# Sheet2.net
KiCad netlist of a schematic drawn in Altium Designer
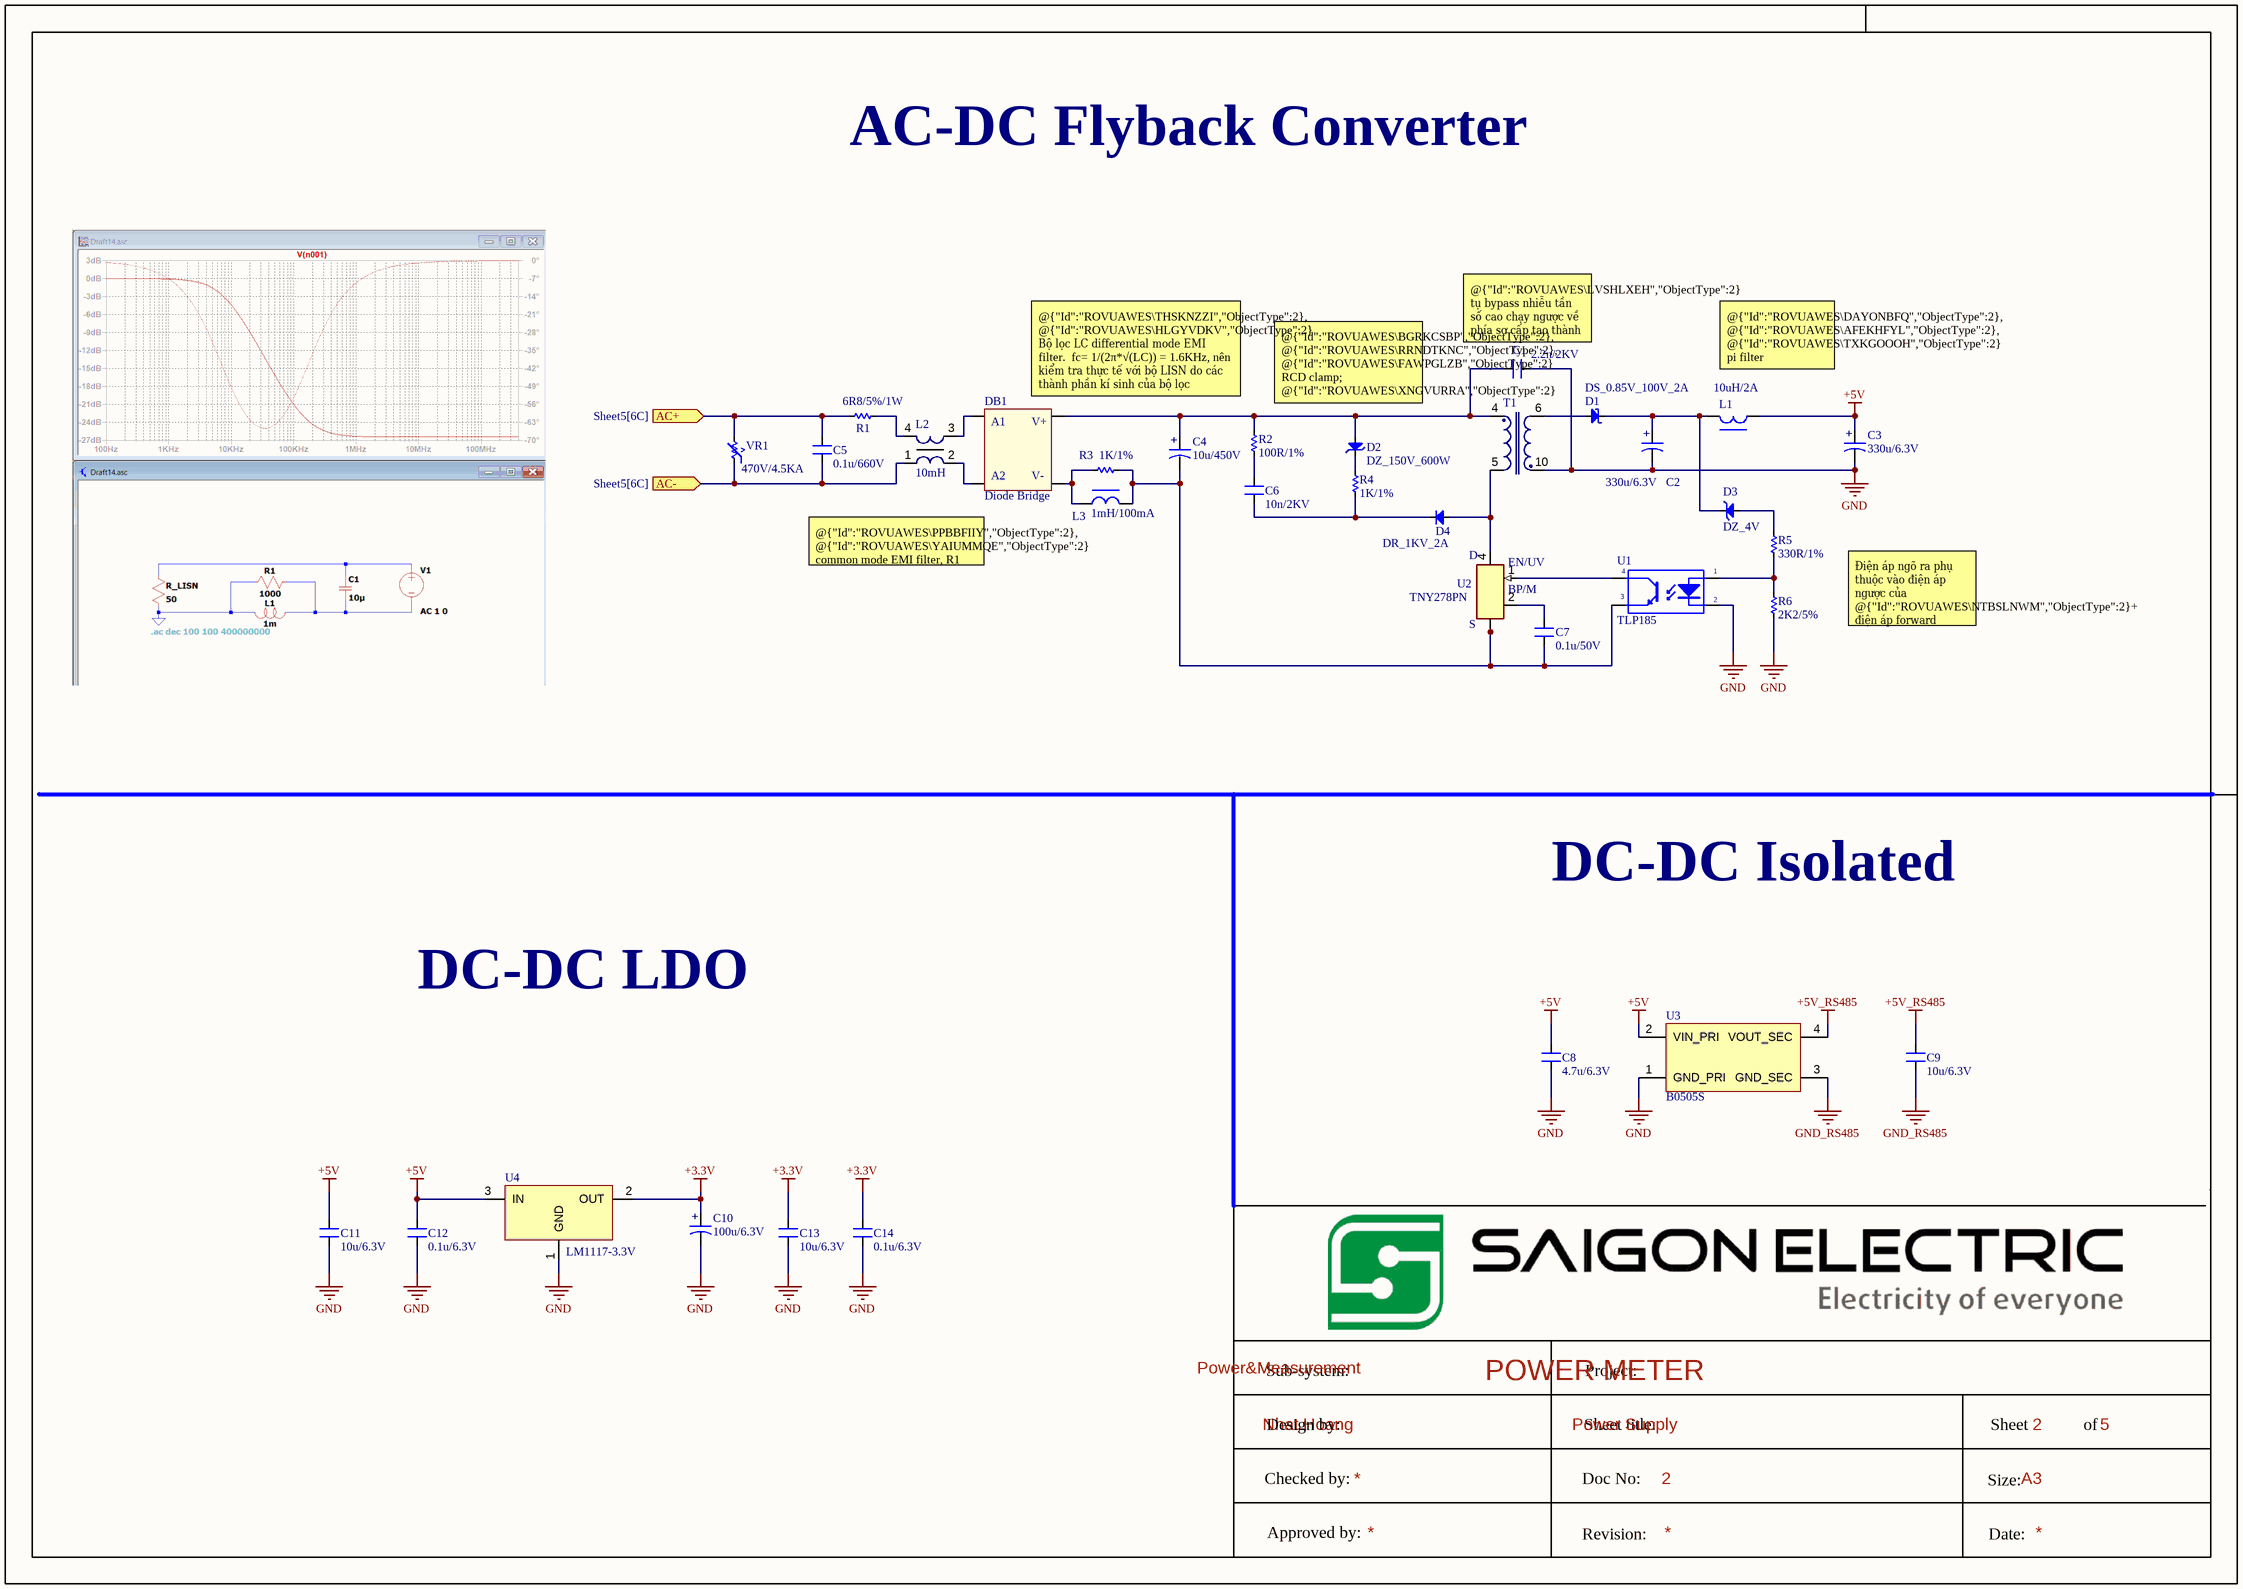
[diagram p0: Sheet2.SchDoc]

(export (version "E")
  (design (tool "Eeschema 10.0.6"))
  (components
    (comp (ref "C1")
      (value "2.2n/2KV")
      (footprint "CN2-B")
      (libsource (lib "DAK_Altium_Integrated_Lib") (part "CAP_SMD"))
    )
    (comp (ref "C2")
      (value "330u/6.3V")
      (footprint "CAPAE9383X105M")
      (fields (field (name "LCSC PART #") "C19606"))
      (libsource (lib "PowerMeter") (part "CAP_POLAR"))
    )
    (comp (ref "C3")
      (value "330u/6.3V")
      (footprint "CAPAE9383X105M")
      (fields (field (name "LCSC PART #") "C19606"))
      (libsource (lib "PowerMeter") (part "CAP_POLAR"))
    )
    (comp (ref "C4")
      (value "10u/450V")
      (footprint "CA-ALU-10BL")
      (libsource (lib "PowerMeter") (part "CAP_POLAR"))
    )
    (comp (ref "C5")
      (value "0.1u/660V")
      (footprint "CAPRR1500W60L1750T900H1600")
      (libsource (lib "DAK_Altium_Integrated_Lib") (part "CAP_SMD"))
    )
    (comp (ref "C6")
      (value "10n/2KV")
      (footprint "CAPRB750W60L1450T500H1850")
      (libsource (lib "DAK_Altium_Integrated_Lib") (part "CAP_SMD"))
    )
    (comp (ref "C7")
      (value "0.1u/50V")
      (footprint "RES_C_3216X70")
      (libsource (lib "DAK_Altium_Integrated_Lib") (part "CAP_SMD"))
    )
    (comp (ref "C8")
      (value "4.7u/6.3V")
      (footprint "CAP_C_2012X110")
      (libsource (lib "DAK_Altium_Integrated_Lib") (part "CAP_SMD"))
    )
    (comp (ref "C9")
      (value "10u/6.3V")
      (footprint "CAP_C_2012X110")
      (libsource (lib "DAK_Altium_Integrated_Lib") (part "CAP_SMD"))
    )
    (comp (ref "C10")
      (value "100u/6.3V")
      (footprint "CAP-ALU-SMD-6.3x7.7x2.2")
      (libsource (lib "PowerMeter") (part "CAP_POLAR"))
    )
    (comp (ref "C11")
      (value "10u/6.3V")
      (footprint "CAP_C_2012X110")
      (libsource (lib "DAK_Altium_Integrated_Lib") (part "CAP_SMD"))
    )
    (comp (ref "C12")
      (value "0.1u/6.3V")
      (footprint "CAP_C_2012X110")
      (libsource (lib "DAK_Altium_Integrated_Lib") (part "CAP_SMD"))
    )
    (comp (ref "C13")
      (value "10u/6.3V")
      (footprint "CAP_C_2012X110")
      (libsource (lib "DAK_Altium_Integrated_Lib") (part "CAP_SMD"))
    )
    (comp (ref "C14")
      (value "0.1u/6.3V")
      (footprint "CAP_C_2012X110")
      (libsource (lib "DAK_Altium_Integrated_Lib") (part "CAP_SMD"))
    )
    (comp (ref "D1")
      (value "DS_0.85V_100V_2A")
      (footprint "DIOM5025X26N")
      (description "Schottky")
      (libsource (lib "PowerMeter") (part "DIODE schottky"))
    )
    (comp (ref "D2")
      (value "DZ_150V_600W")
      (footprint "DIOM4436X26N")
      (description "Zenner")
      (libsource (lib "PowerMeter") (part "DIODE Zener"))
    )
    (comp (ref "D3")
      (value "DZ_4V")
      (footprint "LL-34")
      (description "Zenner")
      (libsource (lib "PowerMeter") (part "DIODE Zener"))
    )
    (comp (ref "D4")
      (value "DR_1KV_2A")
      (footprint "DIOM5025X26N")
      (description "Default Diode")
      (fields (field (name "PUBLISHER") "Altium Limited"))
      (libsource (lib "Library") (part "Diode"))
    )
    (comp (ref "DB1")
      (value "Diode Bridge")
      (footprint "diode bridge 2A")
      (description "Convert AC to DC voltage, 4 pin")
      (libsource (lib "PowerMeter") (part "DIODE BRIGDE"))
    )
    (comp (ref "L1")
      (value "10uH/2A")
      (footprint "L-DIP-M-10")
      (description "Inductor")
      (libsource (lib "Library") (part "L-DIP-1"))
    )
    (comp (ref "L2")
      (value "10mH")
      (footprint "UU98LFH142LF")
      (fields
        (field (name "PARTNO") "744284100")
        (field (name "MANUFACTURER") "Würth Elektronik eiSos GmbH")
        (field (name "CREATED BY") "Christin Zierenner")
      )
      (libsource (lib "Library") (part "L-DIP-2"))
    )
    (comp (ref "L3")
      (value "1mH/100mA")
      (footprint "L-DIP-M-10")
      (description "Inductor")
      (libsource (lib "Library") (part "L-DIP-1"))
    )
    (comp (ref "R1")
      (value "6R8/5%/1W")
      (footprint "RES-1W")
      (description "Resistor")
      (fields
        (field (name "MANUFACTURER") "Generic Components")
        (field (name "PUBLISHER") "Altium Hobart Technology Centre")
      )
      (libsource (lib "Library") (part "Res-SMD"))
    )
    (comp (ref "R2")
      (value "100R/1%")
      (footprint "RES_C_3216X70")
      (description "Resistor")
      (fields
        (field (name "MANUFACTURER") "Generic Components")
        (field (name "PUBLISHER") "Altium Hobart Technology Centre")
      )
      (libsource (lib "Library") (part "Res-SMD"))
    )
    (comp (ref "R3")
      (value "1K/1%")
      (footprint "RES_C_3216X70")
      (description "Resistor")
      (fields
        (field (name "MANUFACTURER") "Generic Components")
        (field (name "PUBLISHER") "Altium Hobart Technology Centre")
      )
      (libsource (lib "Library") (part "Res-SMD"))
    )
    (comp (ref "R4")
      (value "1K/1%")
      (footprint "RES_C_3216X70")
      (description "Resistor")
      (fields
        (field (name "MANUFACTURER") "Generic Components")
        (field (name "PUBLISHER") "Altium Hobart Technology Centre")
      )
      (libsource (lib "Library") (part "Res-SMD"))
    )
    (comp (ref "R5")
      (value "330R/1%")
      (footprint "RES_C_2012X65")
      (description "Resistor")
      (fields
        (field (name "MANUFACTURER") "Generic Components")
        (field (name "PUBLISHER") "Altium Hobart Technology Centre")
      )
      (libsource (lib "Library") (part "Res-SMD"))
    )
    (comp (ref "R6")
      (value "2K2/5%")
      (footprint "RES_C_2012X65")
      (description "Resistor")
      (fields
        (field (name "MANUFACTURER") "Generic Components")
        (field (name "PUBLISHER") "Altium Hobart Technology Centre")
      )
      (libsource (lib "Library") (part "Res-SMD"))
    )
    (comp (ref "T1")
      (value "~")
      (footprint "BOBBIN_EE13/6/6")
      (description "Off-Line Transformer WE-UNIT , L=2.5mH")
      (fields
        (field (name "PARTNO") "7491181012")
        (field (name "MANUFACTURER") "Würth Elektronik eiSos GmbH")
        (field (name "CREATED BY") "Otto Christin")
      )
      (libsource (lib "PowerMeter") (part "Trans"))
    )
    (comp (ref "U1")
      (value "TLP185")
      (footprint "SOP254P700X220-4N")
      (description "Single Opto")
      (libsource (lib "PowerMeter") (part "TLP185"))
    )
    (comp (ref "U2")
      (value "TNY278PN")
      (footprint "IC_TNY274PN")
      (fields (field (name "MP") "TNY284DG"))
      (libsource (lib "PowerMeter") (part "TNY284DG"))
    )
    (comp (ref "U3") (value "B0505S") (footprint "B0505S-1W") (libsource (lib "PowerMeter") (part "B0505S")))
    (comp (ref "U4")
      (value "LM1117-3.3V")
      (footprint "SOT230P700X180-4N")
      (description "800mA Low-Dropout Linear Regulator")
      (fields (field (name "CREATOR") "Nguyen Ba Bien"))
      (libsource (lib "PowerMeter") (part "LM1117"))
    )
    (comp (ref "VR1")
      (value "470V/4.5KA")
      (footprint "B72214P2301K101")
      (description "MOV-14D471K, Varistors 470V 14mm")
      (libsource (lib "PowerMeter") (part "Varistor"))
    )
  )
  (nets
    (net (code "1") (name "+3.3V") (class "Default")
      (node (ref "C10") (pin "1") (pinfunction "1_1") (pintype "passive"))
      (node (ref "C13") (pin "2") (pinfunction "2_2") (pintype "passive"))
      (node (ref "C14") (pin "2") (pinfunction "2_2") (pintype "passive"))
      (node (ref "U4") (pin "2") (pinfunction "OUT_2") (pintype "passive"))
    )
    (net (code "2") (name "+5V") (class "Default")
      (node (ref "C11") (pin "2") (pinfunction "2_2") (pintype "passive"))
      (node (ref "C12") (pin "2") (pinfunction "2_2") (pintype "passive"))
      (node (ref "C3") (pin "1") (pinfunction "1_1") (pintype "passive"))
      (node (ref "C8") (pin "2") (pinfunction "2_2") (pintype "passive"))
      (node (ref "L1") (pin "1") (pinfunction "1_1") (pintype "passive"))
      (node (ref "U3") (pin "2") (pinfunction "VIN_PRI_2") (pintype "passive"))
      (node (ref "U4") (pin "3") (pinfunction "IN_3") (pintype "passive"))
    )
    (net (code "3") (name "+5V_RS485") (class "Default")
      (node (ref "C9") (pin "2") (pinfunction "2_2") (pintype "passive"))
      (node (ref "U3") (pin "4") (pinfunction "VOUT_SEC_4") (pintype "passive"))
    )
    (net (code "4") (name "/AC+") (class "Default")
      (node (ref "C5") (pin "2") (pinfunction "2_2") (pintype "passive"))
      (node (ref "R1") (pin "1") (pinfunction "1_1") (pintype "passive"))
      (node (ref "VR1") (pin "1") (pinfunction "1_1") (pintype "passive"))
    )
    (net (code "5") (name "/AC-") (class "Default")
      (node (ref "C5") (pin "1") (pinfunction "1_1") (pintype "passive"))
      (node (ref "L2") (pin "1") (pinfunction "1_1") (pintype "passive"))
      (node (ref "VR1") (pin "2") (pinfunction "2_2") (pintype "passive"))
    )
    (net (code "6") (name "GND") (class "Default")
      (node (ref "C1") (pin "1") (pinfunction "1_1") (pintype "passive"))
      (node (ref "C10") (pin "2") (pinfunction "2_2") (pintype "passive"))
      (node (ref "C11") (pin "1") (pinfunction "1_1") (pintype "passive"))
      (node (ref "C12") (pin "1") (pinfunction "1_1") (pintype "passive"))
      (node (ref "C13") (pin "1") (pinfunction "1_1") (pintype "passive"))
      (node (ref "C14") (pin "1") (pinfunction "1_1") (pintype "passive"))
      (node (ref "C2") (pin "2") (pinfunction "2_2") (pintype "passive"))
      (node (ref "C3") (pin "2") (pinfunction "2_2") (pintype "passive"))
      (node (ref "C8") (pin "1") (pinfunction "1_1") (pintype "passive"))
      (node (ref "R6") (pin "2") (pinfunction "2_2") (pintype "passive"))
      (node (ref "T1") (pin "10") (pinfunction "10_10") (pintype "passive"))
      (node (ref "U1") (pin "2") (pinfunction "K_2") (pintype "passive"))
      (node (ref "U3") (pin "1") (pinfunction "GND_PRI_1") (pintype "passive"))
      (node (ref "U4") (pin "1") (pinfunction "GND_1") (pintype "passive"))
    )
    (net (code "7") (name "GND_RS485") (class "Default")
      (node (ref "C9") (pin "1") (pinfunction "1_1") (pintype "passive"))
      (node (ref "U3") (pin "3") (pinfunction "GND_SEC_3") (pintype "passive"))
    )
    (net (code "8") (name "Net-(C6-Pad2)") (class "Default")
      (node (ref "C6") (pin "2") (pinfunction "2_2") (pintype "passive"))
      (node (ref "R2") (pin "2") (pinfunction "2_2") (pintype "passive"))
    )
    (net (code "9") (name "Net-(D1-A)") (class "Default")
      (node (ref "D1") (pin "2") (pinfunction "A_2") (pintype "passive"))
      (node (ref "T1") (pin "6") (pinfunction "6_6") (pintype "passive"))
    )
    (net (code "10") (name "Net-(D1-K)") (class "Default")
      (node (ref "C2") (pin "1") (pinfunction "1_1") (pintype "passive"))
      (node (ref "D1") (pin "1") (pinfunction "K_1") (pintype "passive"))
      (node (ref "D3") (pin "1") (pinfunction "K_1") (pintype "passive"))
      (node (ref "L1") (pin "2") (pinfunction "2_2") (pintype "passive"))
    )
    (net (code "11") (name "Net-(D2-A)") (class "Default")
      (node (ref "C1") (pin "2") (pinfunction "2_2") (pintype "passive"))
      (node (ref "C4") (pin "1") (pinfunction "1_1") (pintype "passive"))
      (node (ref "D2") (pin "2") (pinfunction "A_2") (pintype "passive"))
      (node (ref "DB1") (pin "1") (pinfunction "+V_OUT_1") (pintype "passive"))
      (node (ref "R2") (pin "1") (pinfunction "1_1") (pintype "passive"))
      (node (ref "T1") (pin "4") (pinfunction "4_4") (pintype "passive"))
    )
    (net (code "12") (name "Net-(D2-K)") (class "Default")
      (node (ref "D2") (pin "1") (pinfunction "K_1") (pintype "passive"))
      (node (ref "R4") (pin "1") (pinfunction "1_1") (pintype "passive"))
    )
    (net (code "13") (name "Net-(D3-A)") (class "Default")
      (node (ref "D3") (pin "2") (pinfunction "A_2") (pintype "passive"))
      (node (ref "R5") (pin "1") (pinfunction "1_1") (pintype "passive"))
    )
    (net (code "14") (name "Net-(D4-A)") (class "Default")
      (node (ref "D4") (pin "1") (pinfunction "A_1") (pintype "passive"))
      (node (ref "T1") (pin "5") (pinfunction "5_5") (pintype "passive"))
      (node (ref "U2") (pin "4") (pinfunction "D_4") (pintype "passive"))
    )
    (net (code "15") (name "Net-(D4-K)") (class "Default")
      (node (ref "C6") (pin "1") (pinfunction "1_1") (pintype "passive"))
      (node (ref "D4") (pin "2") (pinfunction "K_2") (pintype "passive"))
      (node (ref "R4") (pin "2") (pinfunction "2_2") (pintype "passive"))
    )
    (net (code "16") (name "Net-(DB1--V_OUT)") (class "Default")
      (node (ref "DB1") (pin "2") (pinfunction "-V_OUT_2") (pintype "passive"))
      (node (ref "L3") (pin "1") (pinfunction "1_1") (pintype "passive"))
      (node (ref "R3") (pin "2") (pinfunction "2_2") (pintype "passive"))
    )
    (net (code "17") (name "Net-(DB1-AC1)") (class "Default")
      (node (ref "DB1") (pin "3") (pinfunction "AC1_3") (pintype "passive"))
      (node (ref "L2") (pin "3") (pinfunction "3_3") (pintype "passive"))
    )
    (net (code "18") (name "Net-(DB1-AC2)") (class "Default")
      (node (ref "DB1") (pin "4") (pinfunction "AC2_4") (pintype "passive"))
      (node (ref "L2") (pin "2") (pinfunction "2_2") (pintype "passive"))
    )
    (net (code "19") (name "Net-(L2-Pad4)") (class "Default")
      (node (ref "L2") (pin "4") (pinfunction "4_4") (pintype "passive"))
      (node (ref "R1") (pin "2") (pinfunction "2_2") (pintype "passive"))
    )
    (net (code "20") (name "Net-(U1-A)") (class "Default")
      (node (ref "R5") (pin "2") (pinfunction "2_2") (pintype "passive"))
      (node (ref "R6") (pin "1") (pinfunction "1_1") (pintype "passive"))
      (node (ref "U1") (pin "1") (pinfunction "A_1") (pintype "passive"))
    )
    (net (code "21") (name "Net-(U1-C)") (class "Default")
      (node (ref "U1") (pin "4") (pinfunction "C_4") (pintype "passive"))
      (node (ref "U2") (pin "1") (pinfunction "EN/UV_1") (pintype "input"))
    )
    (net (code "22") (name "Net-(U1-E)") (class "Default")
      (node (ref "C4") (pin "2") (pinfunction "2_2") (pintype "passive"))
      (node (ref "C7") (pin "1") (pinfunction "1_1") (pintype "passive"))
      (node (ref "L3") (pin "2") (pinfunction "2_2") (pintype "passive"))
      (node (ref "R3") (pin "1") (pinfunction "1_1") (pintype "passive"))
      (node (ref "U1") (pin "3") (pinfunction "E_3") (pintype "passive"))
      (node (ref "U2") (pin "5") (pinfunction "S_5") (pintype "passive"))
      (node (ref "U2") (pin "6") (pinfunction "S_6") (pintype "passive"))
      (node (ref "U2") (pin "7") (pinfunction "S_7") (pintype "passive"))
      (node (ref "U2") (pin "8") (pinfunction "S_8") (pintype "passive"))
    )
    (net (code "23") (name "Net-(U2-BP{slash}M)") (class "Default")
      (node (ref "C7") (pin "2") (pinfunction "2_2") (pintype "passive"))
      (node (ref "U2") (pin "2") (pinfunction "BP/M_2") (pintype "passive"))
    )
  )
)
